# 20326.net
KiCad netlist of a schematic drawn in Altium Designer
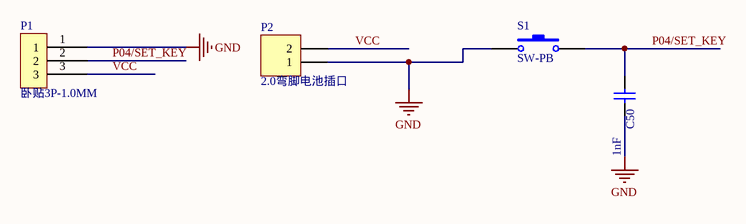
[diagram p0: 把手锁设置板20326.SchDoc]

(export (version "E")
  (design (tool "Eeschema 10.0.6"))
  (components
    (comp (ref "C50")
      (value "1nF")
      (footprint "0603C")
      (description "Capacitor, Ceramic")
      (fields (field (name "TOLERANCE") "5 %"))
      (libsource (lib "MyLibrary") (part "CAP-NP"))
    )
    (comp (ref "P1")
      (value "卧贴3P-1.0MM")
      (footprint "3P-2.54MM")
      (libsource (lib "885阿里云PCB_Project1") (part "3P"))
    )
    (comp (ref "P2")
      (value "2.0弯脚电池插口")
      (footprint "S2B-PH")
      (description "Header, 2-Pin")
      (fields (field (name "PUBLISHER") "Altium Limited"))
      (libsource (lib "保险箱STM32") (part "Header 2"))
    )
    (comp (ref "S1")
      (value "SW-PB")
      (footprint "6*6H9")
      (description "Switch")
      (fields (field (name "PUBLISHER") "Altium Limited"))
      (libsource (lib "Miscellaneous Devices") (part "SW-PB"))
    )
  )
  (nets
    (net (code "1") (name "/P04{slash}SET_KEY") (class "Default")
      (node (ref "C50") (pin "1") (pinfunction "1_1") (pintype "passive"))
      (node (ref "P1") (pin "2") (pinfunction "2_2") (pintype "passive"))
      (node (ref "S1") (pin "2") (pinfunction "2_2") (pintype "passive"))
    )
    (net (code "2") (name "/VCC") (class "Default")
      (node (ref "P1") (pin "3") (pinfunction "3_3") (pintype "passive"))
      (node (ref "P2") (pin "2") (pinfunction "2_2") (pintype "passive"))
    )
    (net (code "3") (name "GND") (class "Default")
      (node (ref "C50") (pin "2") (pinfunction "2_2") (pintype "passive"))
      (node (ref "P1") (pin "1") (pinfunction "1_1") (pintype "passive"))
      (node (ref "P2") (pin "1") (pinfunction "1_1") (pintype "passive"))
      (node (ref "S1") (pin "1") (pinfunction "1_1") (pintype "passive"))
    )
  )
)
